# Flight_Controller_Auxiliary_Board.net
KiCad netlist of a schematic drawn in EAGLE
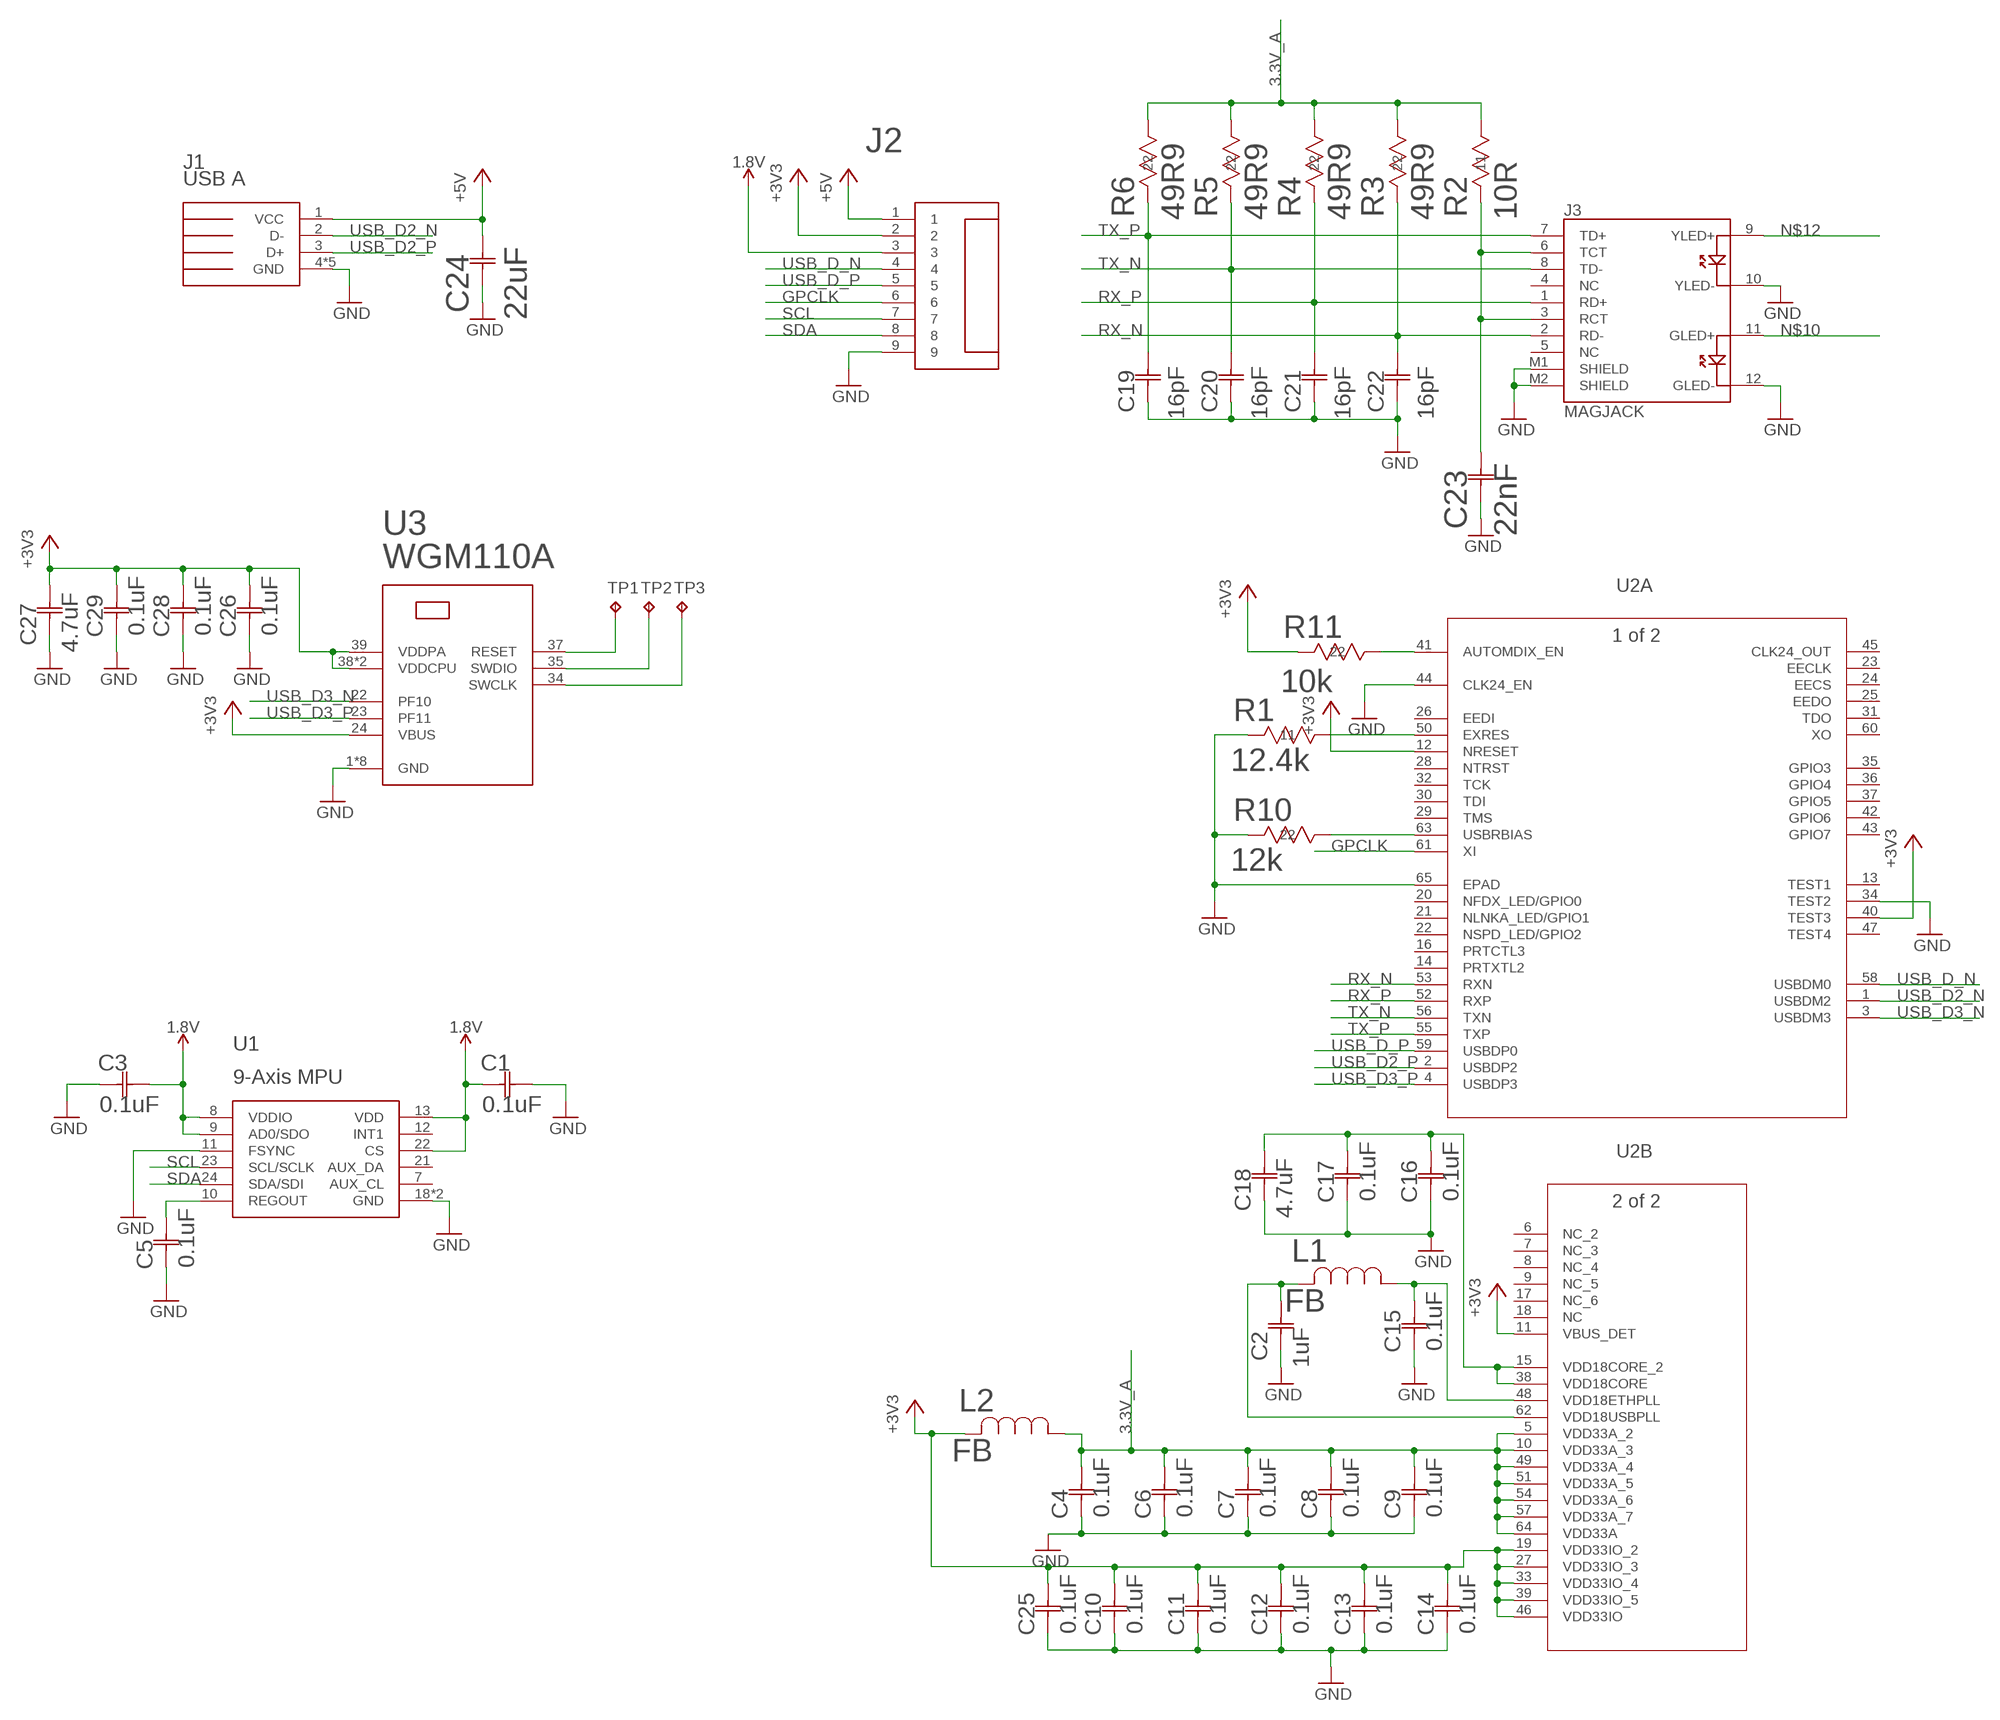
[diagram p0: schematic, sheet 1]

(export (version "E")
  (design (tool "Eeschema 10.0.6"))
  (components
    (comp (ref "C1")
      (value "0.1uF")
      (footprint "eagle-import:0402-M")
      (fields (field (name "MANUFACTURER_PART_NUMBER") "0402ZD104KAT2A"))
      (libsource (lib "eagle-import") (part "0402ZD104KAT2A0402-M"))
    )
    (comp (ref "C2")
      (value "1uF")
      (footprint "eagle-import:YAG_CC0805")
      (fields
        (field (name "MANUFACTURER_PART_NUMBER") "CC0805KKX7R7BB105")
        (field (name "COPYRIGHT") "Copyright C 2015 Accelerated Designs. All rights reserved")
      )
      (libsource (lib "eagle-import") (part "CC0805KKX7R7BB105"))
    )
    (comp (ref "C3")
      (value "0.1uF")
      (footprint "eagle-import:0402-M")
      (fields (field (name "MANUFACTURER_PART_NUMBER") "0402ZD104KAT2A"))
      (libsource (lib "eagle-import") (part "0402ZD104KAT2A0402-M"))
    )
    (comp (ref "C4")
      (value "0.1uF")
      (footprint "eagle-import:0402-M")
      (fields (field (name "MANUFACTURER_PART_NUMBER") "0402ZD104KAT2A"))
      (libsource (lib "eagle-import") (part "0402ZD104KAT2A0402-M"))
    )
    (comp (ref "C5")
      (value "0.1uF")
      (footprint "eagle-import:0402-M")
      (fields (field (name "MANUFACTURER_PART_NUMBER") "0402ZD104KAT2A"))
      (libsource (lib "eagle-import") (part "0402ZD104KAT2A0402-M"))
    )
    (comp (ref "C6")
      (value "0.1uF")
      (footprint "eagle-import:0402-M")
      (fields (field (name "MANUFACTURER_PART_NUMBER") "0402ZD104KAT2A"))
      (libsource (lib "eagle-import") (part "0402ZD104KAT2A0402-M"))
    )
    (comp (ref "C7")
      (value "0.1uF")
      (footprint "eagle-import:0402-M")
      (fields (field (name "MANUFACTURER_PART_NUMBER") "0402ZD104KAT2A"))
      (libsource (lib "eagle-import") (part "0402ZD104KAT2A0402-M"))
    )
    (comp (ref "C8")
      (value "0.1uF")
      (footprint "eagle-import:0402-M")
      (fields (field (name "MANUFACTURER_PART_NUMBER") "0402ZD104KAT2A"))
      (libsource (lib "eagle-import") (part "0402ZD104KAT2A0402-M"))
    )
    (comp (ref "C9")
      (value "0.1uF")
      (footprint "eagle-import:0402-M")
      (fields (field (name "MANUFACTURER_PART_NUMBER") "0402ZD104KAT2A"))
      (libsource (lib "eagle-import") (part "0402ZD104KAT2A0402-M"))
    )
    (comp (ref "C10")
      (value "0.1uF")
      (footprint "eagle-import:0402-M")
      (fields (field (name "MANUFACTURER_PART_NUMBER") "0402ZD104KAT2A"))
      (libsource (lib "eagle-import") (part "0402ZD104KAT2A0402-M"))
    )
    (comp (ref "C11")
      (value "0.1uF")
      (footprint "eagle-import:0402-M")
      (fields (field (name "MANUFACTURER_PART_NUMBER") "0402ZD104KAT2A"))
      (libsource (lib "eagle-import") (part "0402ZD104KAT2A0402-M"))
    )
    (comp (ref "C12")
      (value "0.1uF")
      (footprint "eagle-import:0402-M")
      (fields (field (name "MANUFACTURER_PART_NUMBER") "0402ZD104KAT2A"))
      (libsource (lib "eagle-import") (part "0402ZD104KAT2A0402-M"))
    )
    (comp (ref "C13")
      (value "0.1uF")
      (footprint "eagle-import:0402-M")
      (fields (field (name "MANUFACTURER_PART_NUMBER") "0402ZD104KAT2A"))
      (libsource (lib "eagle-import") (part "0402ZD104KAT2A0402-M"))
    )
    (comp (ref "C14")
      (value "0.1uF")
      (footprint "eagle-import:0402-M")
      (fields (field (name "MANUFACTURER_PART_NUMBER") "0402ZD104KAT2A"))
      (libsource (lib "eagle-import") (part "0402ZD104KAT2A0402-M"))
    )
    (comp (ref "C15")
      (value "0.1uF")
      (footprint "eagle-import:0402-M")
      (fields (field (name "MANUFACTURER_PART_NUMBER") "0402ZD104KAT2A"))
      (libsource (lib "eagle-import") (part "0402ZD104KAT2A0402-M"))
    )
    (comp (ref "C16")
      (value "0.1uF")
      (footprint "eagle-import:0402-M")
      (fields (field (name "MANUFACTURER_PART_NUMBER") "0402ZD104KAT2A"))
      (libsource (lib "eagle-import") (part "0402ZD104KAT2A0402-M"))
    )
    (comp (ref "C17")
      (value "0.1uF")
      (footprint "eagle-import:0402-M")
      (fields (field (name "MANUFACTURER_PART_NUMBER") "0402ZD104KAT2A"))
      (libsource (lib "eagle-import") (part "0402ZD104KAT2A0402-M"))
    )
    (comp (ref "C18")
      (value "4.7uF")
      (footprint "eagle-import:0603-M")
      (fields (field (name "MANUFACTURER_PART_NUMBER") "06036D475KAT2A"))
      (libsource (lib "eagle-import") (part "06036D475KAT2A0603-M"))
    )
    (comp (ref "C19")
      (value "16pF")
      (footprint "eagle-import:G-155-M")
      (fields (field (name "MANUFACTURER_PART_NUMBER") "GRM1555C1H160JA01D"))
      (libsource (lib "eagle-import") (part "GRM1555C1H160JA01DG-155-M"))
    )
    (comp (ref "C20")
      (value "16pF")
      (footprint "eagle-import:G-155-M")
      (fields (field (name "MANUFACTURER_PART_NUMBER") "GRM1555C1H160JA01D"))
      (libsource (lib "eagle-import") (part "GRM1555C1H160JA01DG-155-M"))
    )
    (comp (ref "C21")
      (value "16pF")
      (footprint "eagle-import:G-155-M")
      (fields (field (name "MANUFACTURER_PART_NUMBER") "GRM1555C1H160JA01D"))
      (libsource (lib "eagle-import") (part "GRM1555C1H160JA01DG-155-M"))
    )
    (comp (ref "C22")
      (value "16pF")
      (footprint "eagle-import:G-155-M")
      (fields (field (name "MANUFACTURER_PART_NUMBER") "GRM1555C1H160JA01D"))
      (libsource (lib "eagle-import") (part "GRM1555C1H160JA01DG-155-M"))
    )
    (comp (ref "C23")
      (value "22nF")
      (footprint "eagle-import:G-155-M")
      (fields (field (name "MANUFACTURER_PART_NUMBER") "GRM155R71H223KA12D"))
      (libsource (lib "eagle-import") (part "GRM155R71H223KA12DG-155-M"))
    )
    (comp (ref "C24")
      (value "22uF")
      (footprint "eagle-import:G-21")
      (fields
        (field (name "MANUFACTURER_PART_NUMBER") "GRM21BR60J226ME39L")
        (field (name "COPYRIGHT") "Copyright C 2015 Accelerated Designs. All rights reserved")
      )
      (libsource (lib "eagle-import") (part "GRM21BR60J226ME39L"))
    )
    (comp (ref "C25")
      (value "0.1uF")
      (footprint "eagle-import:0402-M")
      (fields (field (name "MANUFACTURER_PART_NUMBER") "0402ZD104KAT2A"))
      (libsource (lib "eagle-import") (part "0402ZD104KAT2A0402-M"))
    )
    (comp (ref "C26")
      (value "0.1uF")
      (footprint "eagle-import:0402-M")
      (fields (field (name "MANUFACTURER_PART_NUMBER") "0402ZD104KAT2A"))
      (libsource (lib "eagle-import") (part "0402ZD104KAT2A0402-M"))
    )
    (comp (ref "C27")
      (value "4.7uF")
      (footprint "eagle-import:0603-M")
      (fields (field (name "MANUFACTURER_PART_NUMBER") "06036D475KAT2A"))
      (libsource (lib "eagle-import") (part "06036D475KAT2A0603-M"))
    )
    (comp (ref "C28")
      (value "0.1uF")
      (footprint "eagle-import:0402-M")
      (fields (field (name "MANUFACTURER_PART_NUMBER") "0402ZD104KAT2A"))
      (libsource (lib "eagle-import") (part "0402ZD104KAT2A0402-M"))
    )
    (comp (ref "C29")
      (value "0.1uF")
      (footprint "eagle-import:0402-M")
      (fields (field (name "MANUFACTURER_PART_NUMBER") "0402ZD104KAT2A"))
      (libsource (lib "eagle-import") (part "0402ZD104KAT2A0402-M"))
    )
    (comp (ref "J1")
      (value "USB_A_VERT")
      (footprint "eagle-import:USB_A_VERTICAL")
      (libsource (lib "eagle-import") (part "USB_A_VERT"))
    )
    (comp (ref "J2")
      (value "9POS_FFC_CONNECTOR")
      (footprint "eagle-import:9POS_FFC_CONNECTOR")
      (libsource (lib "eagle-import") (part "9POS_FFC_CONNECTOR"))
    )
    (comp (ref "J3")
      (value "MAGJACK")
      (footprint "eagle-import:MAGJACK")
      (libsource (lib "eagle-import") (part "MAGJACK"))
    )
    (comp (ref "L1")
      (value "FB")
      (footprint "eagle-import:IND_BLM18_0603-M")
      (fields (field (name "MANUFACTURER_PART_NUMBER") "BLM18AG601SN1D"))
      (libsource (lib "eagle-import") (part "BLM18AG601SN1DIND_BLM18_0603-M"))
    )
    (comp (ref "L2")
      (value "FB")
      (footprint "eagle-import:IND_BLM18_0603-M")
      (fields (field (name "MANUFACTURER_PART_NUMBER") "BLM18AG601SN1D"))
      (libsource (lib "eagle-import") (part "BLM18AG601SN1DIND_BLM18_0603-M"))
    )
    (comp (ref "R1")
      (value "12.4k")
      (footprint "eagle-import:YAG_R0402-M")
      (fields (field (name "MANUFACTURER_PART_NUMBER") "RC0402FR0712K4L"))
      (libsource (lib "eagle-import") (part "RC0402FR-0712K4LYAG_R0402-M"))
    )
    (comp (ref "R2")
      (value "10R")
      (footprint "eagle-import:STA_RNCP0805-M")
      (fields
        (field (name "MANUFACTURER_PART_NUMBER") "RNCP0805FTD10R0")
        (field (name "COPYRIGHT") "Copyright C 2015 Accelerated Designs. All rights reserved")
      )
      (libsource (lib "eagle-import") (part "RNCP0805FTD10R0STA_RNCP0805-M"))
    )
    (comp (ref "R3")
      (value "49R9")
      (footprint "eagle-import:RC0402N-M")
      (fields (field (name "MANUFACTURER_PART_NUMBER") "RC0402FR0749K9L"))
      (libsource (lib "eagle-import") (part "RC0402FR-0749K9LRC0402N-M"))
    )
    (comp (ref "R4")
      (value "49R9")
      (footprint "eagle-import:RC0402N-M")
      (fields (field (name "MANUFACTURER_PART_NUMBER") "RC0402FR0749K9L"))
      (libsource (lib "eagle-import") (part "RC0402FR-0749K9LRC0402N-M"))
    )
    (comp (ref "R5")
      (value "49R9")
      (footprint "eagle-import:RC0402N-M")
      (fields (field (name "MANUFACTURER_PART_NUMBER") "RC0402FR0749K9L"))
      (libsource (lib "eagle-import") (part "RC0402FR-0749K9LRC0402N-M"))
    )
    (comp (ref "R6")
      (value "49R9")
      (footprint "eagle-import:RC0402N-M")
      (fields (field (name "MANUFACTURER_PART_NUMBER") "RC0402FR0749K9L"))
      (libsource (lib "eagle-import") (part "RC0402FR-0749K9LRC0402N-M"))
    )
    (comp (ref "R10")
      (value "12k")
      (footprint "eagle-import:RC0402N-M")
      (fields (field (name "MANUFACTURER_PART_NUMBER") "RC0402FR0712KL"))
      (libsource (lib "eagle-import") (part "RC0402FR-0712KLRC0402N-M"))
    )
    (comp (ref "R11")
      (value "10k")
      (footprint "eagle-import:RC0805N")
      (fields
        (field (name "DIGIKEYPARTNUMBER") "P10KDATRND")
        (field (name "MANUFACTURER_PART_NUMBER") "ERA6AEB103V")
        (field (name "TOLERANCE") "0.1%")
        (field (name "COPYRIGHT") "Copyright C 2015 Accelerated Designs. All rights reserved")
      )
      (libsource (lib "eagle-import") (part "ERA-6AEB103V"))
    )
    (comp (ref "TP1")
      (value "TPB2,54")
      (footprint "eagle-import:B2,54")
      (libsource (lib "eagle-import") (part "TPB2,54"))
    )
    (comp (ref "TP2")
      (value "TPB2,54")
      (footprint "eagle-import:B2,54")
      (libsource (lib "eagle-import") (part "TPB2,54"))
    )
    (comp (ref "TP3")
      (value "TPB2,54")
      (footprint "eagle-import:B2,54")
      (libsource (lib "eagle-import") (part "TPB2,54"))
    )
    (comp (ref "U1")
      (value "ICM-20948")
      (footprint "eagle-import:QFN40P300X300X105-25N")
      (libsource (lib "eagle-import") (part "ICM-20948"))
    )
    (comp (ref "U2")
      (value "LAN9512-JZXQFN64_9X9MC-M")
      (footprint "eagle-import:QFN64_9X9MC-M")
      (fields (field (name "MANUFACTURER_PART_NUMBER") "LAN9512JZX"))
      (libsource (lib "eagle-import") (part "LAN9512-JZXQFN64_9X9MC-M"))
    )
    (comp (ref "U3")
      (value "WGM110A")
      (footprint "eagle-import:WGM110A")
      (libsource (lib "eagle-import") (part "WGM110A"))
    )
  )
  (nets
    (net (code "1") (name "+3V3") (class "Default")
      (node (ref "C10") (pin "2") (pinfunction "2_2") (pintype "passive"))
      (node (ref "C11") (pin "2") (pinfunction "2_2") (pintype "passive"))
      (node (ref "C12") (pin "2") (pinfunction "2_2") (pintype "passive"))
      (node (ref "C13") (pin "2") (pinfunction "2_2") (pintype "passive"))
      (node (ref "C14") (pin "2") (pinfunction "2_2") (pintype "passive"))
      (node (ref "C25") (pin "2") (pinfunction "2_2") (pintype "passive"))
      (node (ref "C26") (pin "2") (pinfunction "2_2") (pintype "passive"))
      (node (ref "C27") (pin "2") (pinfunction "2_2") (pintype "passive"))
      (node (ref "C28") (pin "2") (pinfunction "2_2") (pintype "passive"))
      (node (ref "C29") (pin "2") (pinfunction "2_2") (pintype "passive"))
      (node (ref "J2") (pin "2") (pinfunction "2_2") (pintype "bidirectional"))
      (node (ref "L2") (pin "2") (pinfunction "2_2") (pintype "passive"))
      (node (ref "R11") (pin "2") (pinfunction "22_2") (pintype "passive"))
      (node (ref "U2") (pin "11") (pinfunction "VBUS_DET_11") (pintype "power_in"))
      (node (ref "U2") (pin "12") (pinfunction "NRESET_12") (pintype "input"))
      (node (ref "U2") (pin "19") (pinfunction "VDD33IO_2_19") (pintype "power_in"))
      (node (ref "U2") (pin "27") (pinfunction "VDD33IO_3_27") (pintype "power_in"))
      (node (ref "U2") (pin "33") (pinfunction "VDD33IO_4_33") (pintype "power_in"))
      (node (ref "U2") (pin "39") (pinfunction "VDD33IO_5_39") (pintype "power_in"))
      (node (ref "U2") (pin "40") (pinfunction "TEST3_40") (pintype "passive"))
      (node (ref "U2") (pin "46") (pinfunction "VDD33IO_46") (pintype "power_in"))
      (node (ref "U3") (pin "24") (pinfunction "VBUS_24") (pintype "bidirectional"))
      (node (ref "U3") (pin "38") (pinfunction "VDDCPU_38") (pintype "bidirectional"))
      (node (ref "U3") (pin "39") (pinfunction "VDDPA_39") (pintype "bidirectional"))
      (node (ref "U3") (pin "51") (pinfunction "VDDCPU_51") (pintype "bidirectional"))
    )
    (net (code "2") (name "+5V") (class "Default")
      (node (ref "C24") (pin "2") (pinfunction "22_2") (pintype "passive"))
      (node (ref "J1") (pin "1") (pinfunction "VCC_1") (pintype "bidirectional"))
      (node (ref "J2") (pin "1") (pinfunction "1_1") (pintype "bidirectional"))
    )
    (net (code "3") (name "/3.3V_A") (class "Default")
      (node (ref "C4") (pin "2") (pinfunction "2_2") (pintype "passive"))
      (node (ref "C6") (pin "2") (pinfunction "2_2") (pintype "passive"))
      (node (ref "C7") (pin "2") (pinfunction "2_2") (pintype "passive"))
      (node (ref "C8") (pin "2") (pinfunction "2_2") (pintype "passive"))
      (node (ref "C9") (pin "2") (pinfunction "2_2") (pintype "passive"))
      (node (ref "L2") (pin "1") (pinfunction "1_1") (pintype "passive"))
      (node (ref "R2") (pin "2") (pinfunction "22_2") (pintype "passive"))
      (node (ref "R3") (pin "1") (pinfunction "11_1") (pintype "passive"))
      (node (ref "R4") (pin "1") (pinfunction "11_1") (pintype "passive"))
      (node (ref "R5") (pin "1") (pinfunction "11_1") (pintype "passive"))
      (node (ref "R6") (pin "1") (pinfunction "11_1") (pintype "passive"))
      (node (ref "U2") (pin "10") (pinfunction "VDD33A_3_10") (pintype "power_in"))
      (node (ref "U2") (pin "49") (pinfunction "VDD33A_4_49") (pintype "power_in"))
      (node (ref "U2") (pin "5") (pinfunction "VDD33A_2_5") (pintype "power_in"))
      (node (ref "U2") (pin "51") (pinfunction "VDD33A_5_51") (pintype "power_in"))
      (node (ref "U2") (pin "54") (pinfunction "VDD33A_6_54") (pintype "power_in"))
      (node (ref "U2") (pin "57") (pinfunction "VDD33A_7_57") (pintype "power_in"))
      (node (ref "U2") (pin "64") (pinfunction "VDD33A_64") (pintype "power_in"))
    )
    (net (code "4") (name "/GPCLK") (class "Default")
      (node (ref "J2") (pin "6") (pinfunction "6_6") (pintype "bidirectional"))
      (node (ref "U2") (pin "61") (pinfunction "XI_61") (pintype "input"))
    )
    (net (code "5") (name "/N$10") (class "Default")
      (node (ref "J3") (pin "11") (pinfunction "GLED+_11") (pintype "bidirectional"))
    )
    (net (code "6") (name "/N$12") (class "Default")
      (node (ref "J3") (pin "9") (pinfunction "YLED+_9") (pintype "bidirectional"))
    )
    (net (code "7") (name "/RX_N") (class "Default")
      (node (ref "C22") (pin "2") (pinfunction "22_2") (pintype "passive"))
      (node (ref "J3") (pin "2") (pinfunction "RD-_2") (pintype "bidirectional"))
      (node (ref "R3") (pin "2") (pinfunction "22_2") (pintype "passive"))
      (node (ref "U2") (pin "53") (pinfunction "RXN_53") (pintype "bidirectional"))
    )
    (net (code "8") (name "/RX_P") (class "Default")
      (node (ref "C21") (pin "2") (pinfunction "22_2") (pintype "passive"))
      (node (ref "J3") (pin "1") (pinfunction "RD+_1") (pintype "bidirectional"))
      (node (ref "R4") (pin "2") (pinfunction "22_2") (pintype "passive"))
      (node (ref "U2") (pin "52") (pinfunction "RXP_52") (pintype "bidirectional"))
    )
    (net (code "9") (name "/SCL") (class "Default")
      (node (ref "J2") (pin "7") (pinfunction "7_7") (pintype "bidirectional"))
      (node (ref "U1") (pin "23") (pinfunction "SCL/SCLK_23") (pintype "bidirectional"))
    )
    (net (code "10") (name "/SDA") (class "Default")
      (node (ref "J2") (pin "8") (pinfunction "8_8") (pintype "bidirectional"))
      (node (ref "U1") (pin "24") (pinfunction "SDA/SDI_24") (pintype "bidirectional"))
    )
    (net (code "11") (name "/TX_N") (class "Default")
      (node (ref "C20") (pin "2") (pinfunction "22_2") (pintype "passive"))
      (node (ref "J3") (pin "8") (pinfunction "TD-_8") (pintype "bidirectional"))
      (node (ref "R5") (pin "2") (pinfunction "22_2") (pintype "passive"))
      (node (ref "U2") (pin "56") (pinfunction "TXN_56") (pintype "bidirectional"))
    )
    (net (code "12") (name "/TX_P") (class "Default")
      (node (ref "C19") (pin "2") (pinfunction "22_2") (pintype "passive"))
      (node (ref "J3") (pin "7") (pinfunction "TD+_7") (pintype "bidirectional"))
      (node (ref "R6") (pin "2") (pinfunction "22_2") (pintype "passive"))
      (node (ref "U2") (pin "55") (pinfunction "TXP_55") (pintype "bidirectional"))
    )
    (net (code "13") (name "/USB_D2_N") (class "Default")
      (node (ref "J1") (pin "2") (pinfunction "D-_2") (pintype "bidirectional"))
      (node (ref "U2") (pin "1") (pinfunction "USBDM2_1") (pintype "bidirectional"))
    )
    (net (code "14") (name "/USB_D2_P") (class "Default")
      (node (ref "J1") (pin "3") (pinfunction "D+_3") (pintype "bidirectional"))
      (node (ref "U2") (pin "2") (pinfunction "USBDP2_2") (pintype "bidirectional"))
    )
    (net (code "15") (name "/USB_D3_N") (class "Default")
      (node (ref "U2") (pin "3") (pinfunction "USBDM3_3") (pintype "bidirectional"))
      (node (ref "U3") (pin "22") (pinfunction "PF10_22") (pintype "bidirectional"))
    )
    (net (code "16") (name "/USB_D3_P") (class "Default")
      (node (ref "U2") (pin "4") (pinfunction "USBDP3_4") (pintype "bidirectional"))
      (node (ref "U3") (pin "23") (pinfunction "PF11_23") (pintype "bidirectional"))
    )
    (net (code "17") (name "/USB_D_N") (class "Default")
      (node (ref "J2") (pin "4") (pinfunction "4_4") (pintype "bidirectional"))
      (node (ref "U2") (pin "58") (pinfunction "USBDM0_58") (pintype "bidirectional"))
    )
    (net (code "18") (name "/USB_D_P") (class "Default")
      (node (ref "J2") (pin "5") (pinfunction "5_5") (pintype "bidirectional"))
      (node (ref "U2") (pin "59") (pinfunction "USBDP0_59") (pintype "bidirectional"))
    )
    (net (code "19") (name "1.8V") (class "Default")
      (node (ref "C1") (pin "1") (pinfunction "1_1") (pintype "passive"))
      (node (ref "C3") (pin "2") (pinfunction "2_2") (pintype "passive"))
      (node (ref "J2") (pin "3") (pinfunction "3_3") (pintype "bidirectional"))
      (node (ref "U1") (pin "13") (pinfunction "VDD_13") (pintype "bidirectional"))
      (node (ref "U1") (pin "22") (pinfunction "CS_22") (pintype "bidirectional"))
      (node (ref "U1") (pin "8") (pinfunction "VDDIO_8") (pintype "bidirectional"))
      (node (ref "U1") (pin "9") (pinfunction "AD0/SDO_9") (pintype "bidirectional"))
    )
    (net (code "20") (name "GND") (class "Default")
      (node (ref "C1") (pin "2") (pinfunction "2_2") (pintype "passive"))
      (node (ref "C10") (pin "1") (pinfunction "1_1") (pintype "passive"))
      (node (ref "C11") (pin "1") (pinfunction "1_1") (pintype "passive"))
      (node (ref "C12") (pin "1") (pinfunction "1_1") (pintype "passive"))
      (node (ref "C13") (pin "1") (pinfunction "1_1") (pintype "passive"))
      (node (ref "C14") (pin "1") (pinfunction "1_1") (pintype "passive"))
      (node (ref "C15") (pin "1") (pinfunction "1_1") (pintype "passive"))
      (node (ref "C16") (pin "1") (pinfunction "1_1") (pintype "passive"))
      (node (ref "C17") (pin "1") (pinfunction "1_1") (pintype "passive"))
      (node (ref "C18") (pin "1") (pinfunction "1_1") (pintype "passive"))
      (node (ref "C19") (pin "1") (pinfunction "11_1") (pintype "passive"))
      (node (ref "C2") (pin "1") (pinfunction "11_1") (pintype "passive"))
      (node (ref "C20") (pin "1") (pinfunction "11_1") (pintype "passive"))
      (node (ref "C21") (pin "1") (pinfunction "11_1") (pintype "passive"))
      (node (ref "C22") (pin "1") (pinfunction "11_1") (pintype "passive"))
      (node (ref "C23") (pin "1") (pinfunction "11_1") (pintype "passive"))
      (node (ref "C24") (pin "1") (pinfunction "11_1") (pintype "passive"))
      (node (ref "C25") (pin "1") (pinfunction "1_1") (pintype "passive"))
      (node (ref "C26") (pin "1") (pinfunction "1_1") (pintype "passive"))
      (node (ref "C27") (pin "1") (pinfunction "1_1") (pintype "passive"))
      (node (ref "C28") (pin "1") (pinfunction "1_1") (pintype "passive"))
      (node (ref "C29") (pin "1") (pinfunction "1_1") (pintype "passive"))
      (node (ref "C3") (pin "1") (pinfunction "1_1") (pintype "passive"))
      (node (ref "C4") (pin "1") (pinfunction "1_1") (pintype "passive"))
      (node (ref "C5") (pin "1") (pinfunction "1_1") (pintype "passive"))
      (node (ref "C6") (pin "1") (pinfunction "1_1") (pintype "passive"))
      (node (ref "C7") (pin "1") (pinfunction "1_1") (pintype "passive"))
      (node (ref "C8") (pin "1") (pinfunction "1_1") (pintype "passive"))
      (node (ref "C9") (pin "1") (pinfunction "1_1") (pintype "passive"))
      (node (ref "J1") (pin "4") (pinfunction "GND_4") (pintype "bidirectional"))
      (node (ref "J1") (pin "P$5") (pinfunction "GND_P$5") (pintype "bidirectional"))
      (node (ref "J1") (pin "P$6") (pinfunction "GND_P$6") (pintype "bidirectional"))
      (node (ref "J1") (pin "P$7") (pinfunction "GND_P$7") (pintype "bidirectional"))
      (node (ref "J1") (pin "P$8") (pinfunction "GND_P$8") (pintype "bidirectional"))
      (node (ref "J2") (pin "9") (pinfunction "9_9") (pintype "bidirectional"))
      (node (ref "J3") (pin "10") (pinfunction "YLED-_10") (pintype "bidirectional"))
      (node (ref "J3") (pin "12") (pinfunction "GLED-_12") (pintype "bidirectional"))
      (node (ref "J3") (pin "M1") (pinfunction "SHIELD_M1") (pintype "bidirectional"))
      (node (ref "J3") (pin "M2") (pinfunction "SHIELD_M2") (pintype "bidirectional"))
      (node (ref "R1") (pin "1") (pinfunction "11_1") (pintype "passive"))
      (node (ref "R10") (pin "2") (pinfunction "22_2") (pintype "passive"))
      (node (ref "U1") (pin "11") (pinfunction "FSYNC_11") (pintype "bidirectional"))
      (node (ref "U1") (pin "18") (pinfunction "GND_18") (pintype "bidirectional"))
      (node (ref "U1") (pin "20") (pinfunction "GND_20") (pintype "bidirectional"))
      (node (ref "U2") (pin "34") (pinfunction "TEST2_34") (pintype "passive"))
      (node (ref "U2") (pin "44") (pinfunction "CLK24_EN_44") (pintype "input"))
      (node (ref "U2") (pin "65") (pinfunction "EPAD_65") (pintype "passive"))
      (node (ref "U3") (pin "1") (pinfunction "GND_1") (pintype "bidirectional"))
      (node (ref "U3") (pin "16") (pinfunction "GND_16") (pintype "bidirectional"))
      (node (ref "U3") (pin "25") (pinfunction "GND_25") (pintype "bidirectional"))
      (node (ref "U3") (pin "40") (pinfunction "GND_40") (pintype "bidirectional"))
      (node (ref "U3") (pin "42") (pinfunction "GND_42") (pintype "bidirectional"))
      (node (ref "U3") (pin "44") (pinfunction "GND_44") (pintype "bidirectional"))
      (node (ref "U3") (pin "46") (pinfunction "GND_46") (pintype "bidirectional"))
      (node (ref "U3") (pin "48") (pinfunction "GND_48") (pintype "bidirectional"))
    )
    (net (code "21") (name "Net-(C2-22)") (class "Default")
      (node (ref "C2") (pin "2") (pinfunction "22_2") (pintype "passive"))
      (node (ref "L1") (pin "2") (pinfunction "2_2") (pintype "passive"))
      (node (ref "U2") (pin "62") (pinfunction "VDD18USBPLL_62") (pintype "power_in"))
    )
    (net (code "22") (name "Net-(C23-22)") (class "Default")
      (node (ref "C23") (pin "2") (pinfunction "22_2") (pintype "passive"))
      (node (ref "J3") (pin "3") (pinfunction "RCT_3") (pintype "bidirectional"))
      (node (ref "J3") (pin "6") (pinfunction "TCT_6") (pintype "bidirectional"))
      (node (ref "R2") (pin "1") (pinfunction "11_1") (pintype "passive"))
    )
    (net (code "23") (name "Net-(R1-22)") (class "Default")
      (node (ref "R1") (pin "2") (pinfunction "22_2") (pintype "passive"))
      (node (ref "U2") (pin "50") (pinfunction "EXRES_50") (pintype "input"))
    )
    (net (code "24") (name "Net-(R10-11)") (class "Default")
      (node (ref "R10") (pin "1") (pinfunction "11_1") (pintype "passive"))
      (node (ref "U2") (pin "63") (pinfunction "USBRBIAS_63") (pintype "input"))
    )
    (net (code "25") (name "Net-(R11-11)") (class "Default")
      (node (ref "R11") (pin "1") (pinfunction "11_1") (pintype "passive"))
      (node (ref "U2") (pin "41") (pinfunction "AUTOMDIX_EN_41") (pintype "input"))
    )
    (net (code "26") (name "Net-(U1-REGOUT)") (class "Default")
      (node (ref "C5") (pin "2") (pinfunction "2_2") (pintype "passive"))
      (node (ref "U1") (pin "10") (pinfunction "REGOUT_10") (pintype "bidirectional"))
    )
    (net (code "27") (name "Net-(U2B-VDD18CORE)") (class "Default")
      (node (ref "C16") (pin "2") (pinfunction "2_2") (pintype "passive"))
      (node (ref "C17") (pin "2") (pinfunction "2_2") (pintype "passive"))
      (node (ref "C18") (pin "2") (pinfunction "2_2") (pintype "passive"))
      (node (ref "U2") (pin "15") (pinfunction "VDD18CORE_2_15") (pintype "power_in"))
      (node (ref "U2") (pin "38") (pinfunction "VDD18CORE_38") (pintype "power_in"))
    )
    (net (code "28") (name "Net-(U2B-VDD18ETHPLL)") (class "Default")
      (node (ref "C15") (pin "2") (pinfunction "2_2") (pintype "passive"))
      (node (ref "L1") (pin "1") (pinfunction "1_1") (pintype "passive"))
      (node (ref "U2") (pin "48") (pinfunction "VDD18ETHPLL_48") (pintype "power_in"))
    )
    (net (code "29") (name "Net-(U3-RESET)") (class "Default")
      (node (ref "TP1") (pin "TP") (pinfunction "TP_TP") (pintype "input"))
      (node (ref "U3") (pin "37") (pinfunction "RESET_37") (pintype "bidirectional"))
    )
    (net (code "30") (name "Net-(U3-SWCLK)") (class "Default")
      (node (ref "TP3") (pin "TP") (pinfunction "TP_TP") (pintype "input"))
      (node (ref "U3") (pin "34") (pinfunction "SWCLK_34") (pintype "bidirectional"))
    )
    (net (code "31") (name "Net-(U3-SWDIO)") (class "Default")
      (node (ref "TP2") (pin "TP") (pinfunction "TP_TP") (pintype "input"))
      (node (ref "U3") (pin "35") (pinfunction "SWDIO_35") (pintype "bidirectional"))
    )
    (net (code "32") (name "unconnected-(J3-NC-Pad4)") (class "Default")
      (node (ref "J3") (pin "4") (pinfunction "NC_4") (pintype "bidirectional"))
    )
    (net (code "33") (name "unconnected-(J3-NC-Pad5)") (class "Default")
      (node (ref "J3") (pin "5") (pinfunction "NC_5") (pintype "bidirectional"))
    )
    (net (code "34") (name "unconnected-(U1-AUX_CL-Pad7)") (class "Default")
      (node (ref "U1") (pin "7") (pinfunction "AUX_CL_7") (pintype "bidirectional"))
    )
    (net (code "35") (name "unconnected-(U1-AUX_DA-Pad21)") (class "Default")
      (node (ref "U1") (pin "21") (pinfunction "AUX_DA_21") (pintype "bidirectional"))
    )
    (net (code "36") (name "unconnected-(U1-INT1-Pad12)") (class "Default")
      (node (ref "U1") (pin "12") (pinfunction "INT1_12") (pintype "bidirectional"))
    )
    (net (code "37") (name "unconnected-(U2A-CLK24_OUT-Pad45)") (class "Default")
      (node (ref "U2") (pin "45") (pinfunction "CLK24_OUT_45") (pintype "output"))
    )
    (net (code "38") (name "unconnected-(U2A-EECLK-Pad23)") (class "Default")
      (node (ref "U2") (pin "23") (pinfunction "EECLK_23") (pintype "output"))
    )
    (net (code "39") (name "unconnected-(U2A-EECS-Pad24)") (class "Default")
      (node (ref "U2") (pin "24") (pinfunction "EECS_24") (pintype "output"))
    )
    (net (code "40") (name "unconnected-(U2A-EEDI-Pad26)") (class "Default")
      (node (ref "U2") (pin "26") (pinfunction "EEDI_26") (pintype "input"))
    )
    (net (code "41") (name "unconnected-(U2A-EEDO-Pad25)") (class "Default")
      (node (ref "U2") (pin "25") (pinfunction "EEDO_25") (pintype "output"))
    )
    (net (code "42") (name "unconnected-(U2A-GPIO3-Pad35)") (class "Default")
      (node (ref "U2") (pin "35") (pinfunction "GPIO3_35") (pintype "bidirectional"))
    )
    (net (code "43") (name "unconnected-(U2A-GPIO4-Pad36)") (class "Default")
      (node (ref "U2") (pin "36") (pinfunction "GPIO4_36") (pintype "bidirectional"))
    )
    (net (code "44") (name "unconnected-(U2A-GPIO5-Pad37)") (class "Default")
      (node (ref "U2") (pin "37") (pinfunction "GPIO5_37") (pintype "bidirectional"))
    )
    (net (code "45") (name "unconnected-(U2A-GPIO6-Pad42)") (class "Default")
      (node (ref "U2") (pin "42") (pinfunction "GPIO6_42") (pintype "bidirectional"))
    )
    (net (code "46") (name "unconnected-(U2A-GPIO7-Pad43)") (class "Default")
      (node (ref "U2") (pin "43") (pinfunction "GPIO7_43") (pintype "bidirectional"))
    )
    (net (code "47") (name "unconnected-(U2A-NFDX_LED{slash}GPIO0-Pad20)") (class "Default")
      (node (ref "U2") (pin "20") (pinfunction "NFDX_LED/GPIO0_20") (pintype "bidirectional"))
    )
    (net (code "48") (name "unconnected-(U2A-NLNKA_LED{slash}GPIO1-Pad21)") (class "Default")
      (node (ref "U2") (pin "21") (pinfunction "NLNKA_LED/GPIO1_21") (pintype "bidirectional"))
    )
    (net (code "49") (name "unconnected-(U2A-NSPD_LED{slash}GPIO2-Pad22)") (class "Default")
      (node (ref "U2") (pin "22") (pinfunction "NSPD_LED/GPIO2_22") (pintype "bidirectional"))
    )
    (net (code "50") (name "unconnected-(U2A-NTRST-Pad28)") (class "Default")
      (node (ref "U2") (pin "28") (pinfunction "NTRST_28") (pintype "input"))
    )
    (net (code "51") (name "unconnected-(U2A-PRTCTL3-Pad16)") (class "Default")
      (node (ref "U2") (pin "16") (pinfunction "PRTCTL3_16") (pintype "bidirectional"))
    )
    (net (code "52") (name "unconnected-(U2A-PRTXTL2-Pad14)") (class "Default")
      (node (ref "U2") (pin "14") (pinfunction "PRTXTL2_14") (pintype "bidirectional"))
    )
    (net (code "53") (name "unconnected-(U2A-TCK-Pad32)") (class "Default")
      (node (ref "U2") (pin "32") (pinfunction "TCK_32") (pintype "input"))
    )
    (net (code "54") (name "unconnected-(U2A-TDI-Pad30)") (class "Default")
      (node (ref "U2") (pin "30") (pinfunction "TDI_30") (pintype "input"))
    )
    (net (code "55") (name "unconnected-(U2A-TDO-Pad31)") (class "Default")
      (node (ref "U2") (pin "31") (pinfunction "TDO_31") (pintype "output"))
    )
    (net (code "56") (name "unconnected-(U2A-TEST1-Pad13)") (class "Default")
      (node (ref "U2") (pin "13") (pinfunction "TEST1_13") (pintype "passive"))
    )
    (net (code "57") (name "unconnected-(U2A-TEST4-Pad47)") (class "Default")
      (node (ref "U2") (pin "47") (pinfunction "TEST4_47") (pintype "passive"))
    )
    (net (code "58") (name "unconnected-(U2A-TMS-Pad29)") (class "Default")
      (node (ref "U2") (pin "29") (pinfunction "TMS_29") (pintype "input"))
    )
    (net (code "59") (name "unconnected-(U2A-XO-Pad60)") (class "Default")
      (node (ref "U2") (pin "60") (pinfunction "XO_60") (pintype "output"))
    )
    (net (code "60") (name "unconnected-(U2B-NC-Pad18)") (class "Default")
      (node (ref "U2") (pin "18") (pinfunction "NC_18") (pintype "no_connect"))
    )
    (net (code "61") (name "unconnected-(U2B-NC_2-Pad6)") (class "Default")
      (node (ref "U2") (pin "6") (pinfunction "NC_2_6") (pintype "no_connect"))
    )
    (net (code "62") (name "unconnected-(U2B-NC_3-Pad7)") (class "Default")
      (node (ref "U2") (pin "7") (pinfunction "NC_3_7") (pintype "no_connect"))
    )
    (net (code "63") (name "unconnected-(U2B-NC_4-Pad8)") (class "Default")
      (node (ref "U2") (pin "8") (pinfunction "NC_4_8") (pintype "no_connect"))
    )
    (net (code "64") (name "unconnected-(U2B-NC_5-Pad9)") (class "Default")
      (node (ref "U2") (pin "9") (pinfunction "NC_5_9") (pintype "no_connect"))
    )
    (net (code "65") (name "unconnected-(U2B-NC_6-Pad17)") (class "Default")
      (node (ref "U2") (pin "17") (pinfunction "NC_6_17") (pintype "no_connect"))
    )
  )
)
